# TimedCircuit.net
KiCad netlist of a schematic drawn in Altium Designer
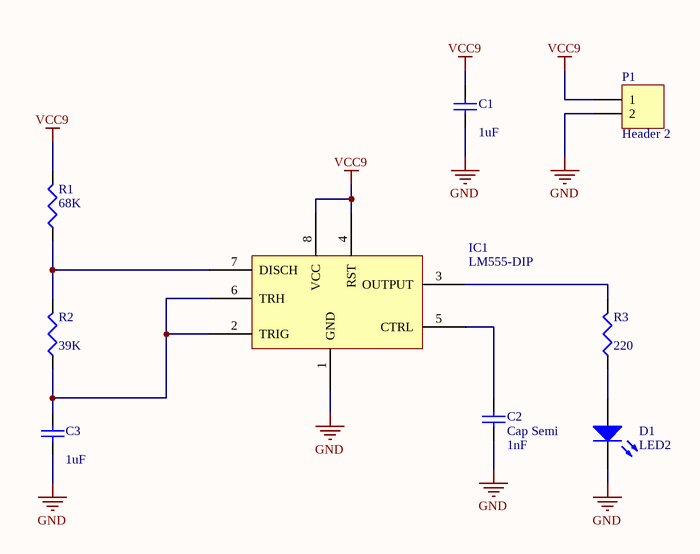
[diagram p0: TimedCircuit.SchDoc]

(export (version "E")
  (design (tool "Eeschema 10.0.6"))
  (components
    (comp (ref "C1")
      (value "1uF")
      (footprint "1608[0603]")
      (description "Capacitor (Semiconductor SIM Model)")
      (fields (field (name "Comment") "Cap Semi") (field (name "PUBLISHER") "Altium Limited"))
      (libsource (lib "Miscellaneous Devices") (part "Cap Semi"))
    )
    (comp (ref "C2")
      (value "Cap Semi")
      (footprint "1608[0603]")
      (description "Capacitor (Semiconductor SIM Model)")
      (fields (field (name "ALTIUM_VALUE") "1nF") (field (name "PUBLISHER") "Altium Limited"))
      (libsource (lib "Miscellaneous Devices") (part "Cap Semi"))
    )
    (comp (ref "C3")
      (value "1uF")
      (footprint "1608[0603]")
      (description "Capacitor (Semiconductor SIM Model)")
      (fields (field (name "Comment") "Cap Semi") (field (name "PUBLISHER") "Altium Limited"))
      (libsource (lib "Miscellaneous Devices") (part "Cap Semi"))
    )
    (comp (ref "D1")
      (value "LED2")
      (footprint "3.2X1.6X1.1")
      (description "Typical RED, GREEN, YELLOW, AMBER GaAs LED")
      (fields (field (name "PUBLISHER") "Altium Limited"))
      (libsource (lib "Miscellaneous Devices") (part "LED2"))
    )
    (comp (ref "IC1")
      (value "LM555-DIP")
      (footprint "DIP-LM555")
      (description "LM555 DIP")
      (libsource (lib "UserSch") (part "LM555-DIP"))
    )
    (comp (ref "P1")
      (value "Header 2")
      (footprint "HDR1X2")
      (description "Header, 2-Pin")
      (fields (field (name "PUBLISHER") "Altium Limited"))
      (libsource (lib "Miscellaneous Connectors") (part "Header 2"))
    )
    (comp (ref "R1")
      (value "68K")
      (footprint "J1-0603")
      (description "Resistor")
      (fields (field (name "Comment") "Res3") (field (name "PUBLISHER") "Altium Limited"))
      (libsource (lib "Miscellaneous Devices") (part "Res3"))
    )
    (comp (ref "R2")
      (value "39K")
      (footprint "J1-0603")
      (description "Resistor")
      (fields (field (name "Comment") "Res3") (field (name "PUBLISHER") "Altium Limited"))
      (libsource (lib "Miscellaneous Devices") (part "Res3"))
    )
    (comp (ref "R3")
      (value "220")
      (footprint "J1-0603")
      (description "Resistor")
      (fields (field (name "Comment") "Res3") (field (name "PUBLISHER") "Altium Limited"))
      (libsource (lib "Miscellaneous Devices") (part "Res3"))
    )
  )
  (nets
    (net (code "1") (name "GND") (class "Default")
      (node (ref "C1") (pin "1") (pinfunction "1_1") (pintype "passive"))
      (node (ref "C2") (pin "1") (pinfunction "1_1") (pintype "passive"))
      (node (ref "C3") (pin "1") (pinfunction "1_1") (pintype "passive"))
      (node (ref "D1") (pin "2") (pinfunction "K_2") (pintype "passive"))
      (node (ref "IC1") (pin "1") (pinfunction "GND_1") (pintype "power_in"))
      (node (ref "P1") (pin "2") (pinfunction "2_2") (pintype "passive"))
    )
    (net (code "2") (name "Net-(D1-A)") (class "Default")
      (node (ref "D1") (pin "1") (pinfunction "A_1") (pintype "passive"))
      (node (ref "R3") (pin "1") (pinfunction "1_1") (pintype "passive"))
    )
    (net (code "3") (name "Net-(IC1-CTRL)") (class "Default")
      (node (ref "C2") (pin "2") (pinfunction "2_2") (pintype "passive"))
      (node (ref "IC1") (pin "5") (pinfunction "CTRL_5") (pintype "power_in"))
    )
    (net (code "4") (name "Net-(IC1-DISCH)") (class "Default")
      (node (ref "IC1") (pin "7") (pinfunction "DISCH_7") (pintype "passive"))
      (node (ref "R1") (pin "1") (pinfunction "1_1") (pintype "passive"))
      (node (ref "R2") (pin "2") (pinfunction "2_2") (pintype "passive"))
    )
    (net (code "5") (name "Net-(IC1-OUTPUT)") (class "Default")
      (node (ref "IC1") (pin "3") (pinfunction "OUTPUT_3") (pintype "passive"))
      (node (ref "R3") (pin "2") (pinfunction "2_2") (pintype "passive"))
    )
    (net (code "6") (name "Net-(IC1-TRH)") (class "Default")
      (node (ref "C3") (pin "2") (pinfunction "2_2") (pintype "passive"))
      (node (ref "IC1") (pin "2") (pinfunction "TRIG_2") (pintype "passive"))
      (node (ref "IC1") (pin "6") (pinfunction "TRH_6") (pintype "passive"))
      (node (ref "R2") (pin "1") (pinfunction "1_1") (pintype "passive"))
    )
    (net (code "7") (name "VCC9") (class "Default")
      (node (ref "C1") (pin "2") (pinfunction "2_2") (pintype "passive"))
      (node (ref "IC1") (pin "4") (pinfunction "RST_4") (pintype "passive"))
      (node (ref "IC1") (pin "8") (pinfunction "VCC_8") (pintype "power_in"))
      (node (ref "P1") (pin "1") (pinfunction "1_1") (pintype "passive"))
      (node (ref "R1") (pin "2") (pinfunction "2_2") (pintype "passive"))
    )
  )
)
